# Adafruit_NeoMatrix_8x8_v2.net
KiCad netlist of a schematic drawn in EAGLE
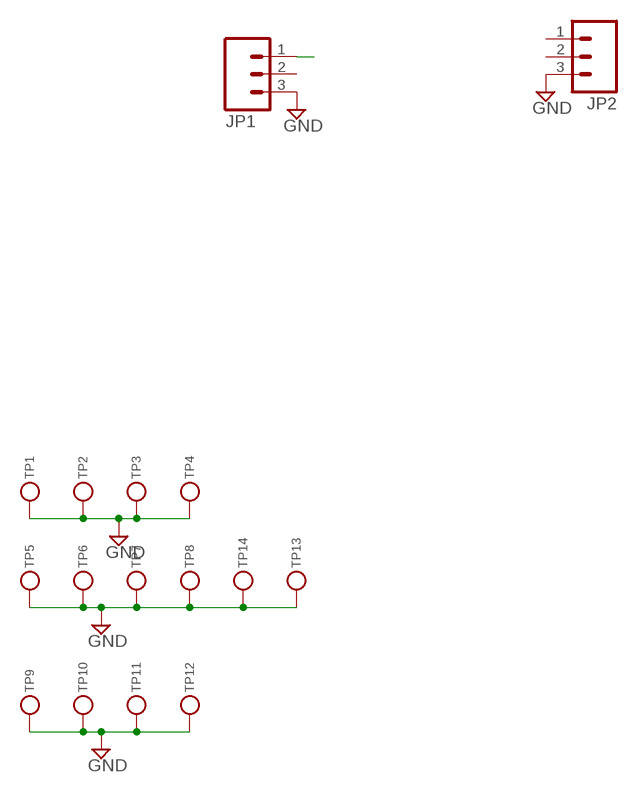
[diagram p0: schematic, sheet 1]

(export (version "E")
  (design (tool "Eeschema 10.0.6"))
  (components
    (comp (ref "JP1")
      (value "M03PTH")
      (footprint "eagle-import:1X03")
      (libsource (lib "eagle-import") (part "M03PTH"))
    )
    (comp (ref "JP2")
      (value "M03PTH")
      (footprint "eagle-import:1X03")
      (libsource (lib "eagle-import") (part "M03PTH"))
    )
    (comp (ref "TP1")
      (value "TESTPOINT")
      (footprint "eagle-import:TESTPOINT_SMT")
      (libsource (lib "eagle-import") (part "TESTPOINT"))
    )
    (comp (ref "TP2")
      (value "TESTPOINT")
      (footprint "eagle-import:TESTPOINT_SMT")
      (libsource (lib "eagle-import") (part "TESTPOINT"))
    )
    (comp (ref "TP3")
      (value "TESTPOINT")
      (footprint "eagle-import:TESTPOINT_SMT")
      (libsource (lib "eagle-import") (part "TESTPOINT"))
    )
    (comp (ref "TP4")
      (value "TESTPOINT")
      (footprint "eagle-import:TESTPOINT_SMT")
      (libsource (lib "eagle-import") (part "TESTPOINT"))
    )
    (comp (ref "TP5")
      (value "TESTPOINT")
      (footprint "eagle-import:TESTPOINT_SMT")
      (libsource (lib "eagle-import") (part "TESTPOINT"))
    )
    (comp (ref "TP6")
      (value "TESTPOINT")
      (footprint "eagle-import:TESTPOINT_SMT")
      (libsource (lib "eagle-import") (part "TESTPOINT"))
    )
    (comp (ref "TP7")
      (value "TESTPOINT")
      (footprint "eagle-import:TESTPOINT_SMT")
      (libsource (lib "eagle-import") (part "TESTPOINT"))
    )
    (comp (ref "TP8")
      (value "TESTPOINT")
      (footprint "eagle-import:TESTPOINT_SMT")
      (libsource (lib "eagle-import") (part "TESTPOINT"))
    )
    (comp (ref "TP9")
      (value "TESTPOINT")
      (footprint "eagle-import:TESTPOINT_SMT")
      (libsource (lib "eagle-import") (part "TESTPOINT"))
    )
    (comp (ref "TP10")
      (value "TESTPOINT")
      (footprint "eagle-import:TESTPOINT_SMT")
      (libsource (lib "eagle-import") (part "TESTPOINT"))
    )
    (comp (ref "TP11")
      (value "TESTPOINT")
      (footprint "eagle-import:TESTPOINT_SMT")
      (libsource (lib "eagle-import") (part "TESTPOINT"))
    )
    (comp (ref "TP12")
      (value "TESTPOINT")
      (footprint "eagle-import:TESTPOINT_SMT")
      (libsource (lib "eagle-import") (part "TESTPOINT"))
    )
    (comp (ref "TP13")
      (value "TESTPOINT")
      (footprint "eagle-import:TESTPOINT_SMT")
      (libsource (lib "eagle-import") (part "TESTPOINT"))
    )
    (comp (ref "TP14")
      (value "TESTPOINT")
      (footprint "eagle-import:TESTPOINT_SMT")
      (libsource (lib "eagle-import") (part "TESTPOINT"))
    )
  )
  (nets
    (net (code "1") (name "GND") (class "Default")
      (node (ref "JP1") (pin "3") (pinfunction "3_3") (pintype "passive"))
      (node (ref "JP2") (pin "3") (pinfunction "3_3") (pintype "passive"))
      (node (ref "TP1") (pin "P$1") (pinfunction "P$1_P$1") (pintype "bidirectional"))
      (node (ref "TP10") (pin "P$1") (pinfunction "P$1_P$1") (pintype "bidirectional"))
      (node (ref "TP11") (pin "P$1") (pinfunction "P$1_P$1") (pintype "bidirectional"))
      (node (ref "TP12") (pin "P$1") (pinfunction "P$1_P$1") (pintype "bidirectional"))
      (node (ref "TP13") (pin "P$1") (pinfunction "P$1_P$1") (pintype "bidirectional"))
      (node (ref "TP14") (pin "P$1") (pinfunction "P$1_P$1") (pintype "bidirectional"))
      (node (ref "TP2") (pin "P$1") (pinfunction "P$1_P$1") (pintype "bidirectional"))
      (node (ref "TP3") (pin "P$1") (pinfunction "P$1_P$1") (pintype "bidirectional"))
      (node (ref "TP4") (pin "P$1") (pinfunction "P$1_P$1") (pintype "bidirectional"))
      (node (ref "TP5") (pin "P$1") (pinfunction "P$1_P$1") (pintype "bidirectional"))
      (node (ref "TP6") (pin "P$1") (pinfunction "P$1_P$1") (pintype "bidirectional"))
      (node (ref "TP7") (pin "P$1") (pinfunction "P$1_P$1") (pintype "bidirectional"))
      (node (ref "TP8") (pin "P$1") (pinfunction "P$1_P$1") (pintype "bidirectional"))
      (node (ref "TP9") (pin "P$1") (pinfunction "P$1_P$1") (pintype "bidirectional"))
    )
    (net (code "2") (name "unconnected-(JP1-Pad1)") (class "Default")
      (node (ref "JP1") (pin "1") (pinfunction "1_1") (pintype "passive"))
    )
    (net (code "3") (name "unconnected-(JP1-Pad2)") (class "Default")
      (node (ref "JP1") (pin "2") (pinfunction "2_2") (pintype "passive"))
    )
    (net (code "4") (name "unconnected-(JP2-Pad1)") (class "Default")
      (node (ref "JP2") (pin "1") (pinfunction "1_1") (pintype "passive"))
    )
    (net (code "5") (name "unconnected-(JP2-Pad2)") (class "Default")
      (node (ref "JP2") (pin "2") (pinfunction "2_2") (pintype "passive"))
    )
  )
)
